# schematic.net
KiCad netlist of a schematic drawn in Altium Designer
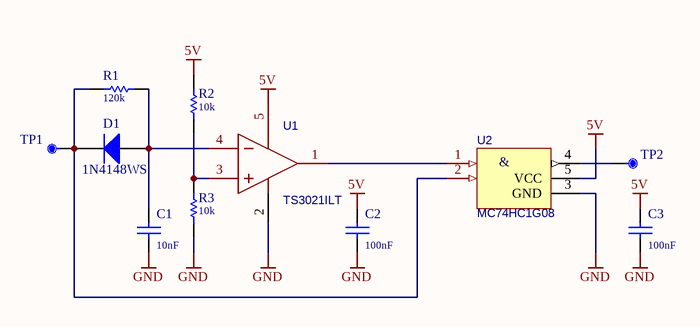
[diagram p0: schematic.SchDoc]

(export (version "E")
  (design (tool "Eeschema 10.0.6"))
  (components
    (comp (ref "C1")
      (value "10nF")
      (footprint "C0603")
      (description "10nF 50V 0603")
      (libsource (lib "Miscellaneous Devices") (part "CAP"))
    )
    (comp (ref "C2")
      (value "100nF")
      (footprint "C0603")
      (description "100nF 50V 0603")
      (libsource (lib "Miscellaneous Devices") (part "CAP"))
    )
    (comp (ref "C3")
      (value "100nF")
      (footprint "C0603")
      (description "100nF 50V 0603")
      (libsource (lib "Miscellaneous Devices") (part "CAP"))
    )
    (comp (ref "D1")
      (value "1N4148WS")
      (footprint "SOD-323")
      (libsource (lib "Miscellaneous Devices") (part "US1M-13-F"))
    )
    (comp (ref "R1")
      (value "120k")
      (footprint "R0603")
      (description "120k 5% 0603")
      (libsource (lib "RR_Passive") (part "RES"))
    )
    (comp (ref "R2")
      (value "10k")
      (footprint "R0603")
      (description "10k 5% 0603")
      (libsource (lib "RR_Passive") (part "RES"))
    )
    (comp (ref "R3")
      (value "10k")
      (footprint "R0603")
      (description "10k 5% 0603")
      (libsource (lib "RR_Passive") (part "RES"))
    )
    (comp (ref "TP1")
      (value "~")
      (footprint "TP2030_SMD")
      (libsource (lib "Miscellaneous Devices") (part "TP_Dup1"))
    )
    (comp (ref "TP2")
      (value "~")
      (footprint "TP2030_SMD")
      (libsource (lib "Miscellaneous Devices") (part "TP_Dup1"))
    )
    (comp (ref "U1")
      (value "TS3021ILT")
      (footprint "SOT-23-5")
      (libsource (lib "altium-import") (part "root_0_TS3021ILT_"))
    )
    (comp (ref "U2")
      (value "MC74HC1G08")
      (footprint "SOT-23-5")
      (libsource (lib "Schlib1") (part "MC74HC1G08DTT1G"))
    )
  )
  (nets
    (net (code "1") (name "5V") (class "Default")
      (node (ref "C2") (pin "2") (pinfunction "2_2") (pintype "passive"))
      (node (ref "C3") (pin "2") (pinfunction "2_2") (pintype "passive"))
      (node (ref "R2") (pin "2") (pinfunction "2_2") (pintype "passive"))
      (node (ref "U1") (pin "5") (pinfunction "VCC+_5") (pintype "passive"))
      (node (ref "U2") (pin "5") (pinfunction "VCC_5") (pintype "passive"))
    )
    (net (code "2") (name "GND") (class "Default")
      (node (ref "C1") (pin "1") (pinfunction "1_1") (pintype "passive"))
      (node (ref "C2") (pin "1") (pinfunction "1_1") (pintype "passive"))
      (node (ref "C3") (pin "1") (pinfunction "1_1") (pintype "passive"))
      (node (ref "R3") (pin "1") (pinfunction "1_1") (pintype "passive"))
      (node (ref "U1") (pin "2") (pinfunction "VCC-_2") (pintype "passive"))
      (node (ref "U2") (pin "3") (pinfunction "GND_3") (pintype "passive"))
    )
    (net (code "3") (name "Net-(D1-A)") (class "Default")
      (node (ref "C1") (pin "2") (pinfunction "2_2") (pintype "passive"))
      (node (ref "D1") (pin "1") (pinfunction "A_1") (pintype "passive"))
      (node (ref "R1") (pin "1") (pinfunction "1_1") (pintype "passive"))
      (node (ref "U1") (pin "4") (pinfunction "IN-_4") (pintype "passive"))
    )
    (net (code "4") (name "Net-(D1-K)") (class "Default")
      (node (ref "D1") (pin "2") (pinfunction "K_2") (pintype "passive"))
      (node (ref "R1") (pin "2") (pinfunction "2_2") (pintype "passive"))
      (node (ref "TP1") (pin "1") (pinfunction "1_1") (pintype "passive"))
      (node (ref "U2") (pin "2") (pinfunction "B_2") (pintype "input"))
    )
    (net (code "5") (name "Net-(U1-IN+)") (class "Default")
      (node (ref "R2") (pin "1") (pinfunction "1_1") (pintype "passive"))
      (node (ref "R3") (pin "2") (pinfunction "2_2") (pintype "passive"))
      (node (ref "U1") (pin "3") (pinfunction "IN+_3") (pintype "passive"))
    )
    (net (code "6") (name "Net-(U1-OUT)") (class "Default")
      (node (ref "U1") (pin "1") (pinfunction "OUT_1") (pintype "passive"))
      (node (ref "U2") (pin "1") (pinfunction "A_1") (pintype "input"))
    )
    (net (code "7") (name "Net-(U2-Y)") (class "Default")
      (node (ref "TP2") (pin "1") (pinfunction "1_1") (pintype "passive"))
      (node (ref "U2") (pin "4") (pinfunction "Y_4") (pintype "output"))
    )
  )
)
